# DEC8i-buscon.net
KiCad netlist of a schematic drawn in EAGLE
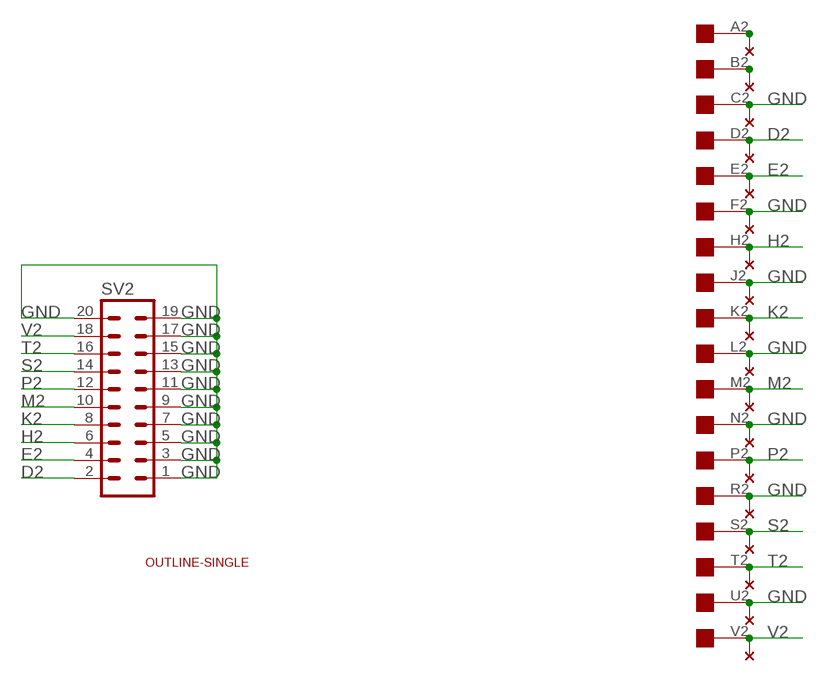
[diagram p0: schematic, sheet 1]

(export (version "E")
  (design (tool "Eeschema 10.0.6"))
  (components
    (comp (ref "SV2")
      (value "MA10-2")
      (footprint "eagle-import:MA10-2")
      (libsource (lib "eagle-import") (part "MA10-2"))
    )
    (comp (ref "U$4")
      (value "EDGE-1")
      (footprint "eagle-import:EDGE-CON1")
      (libsource (lib "eagle-import") (part "EDGE-1"))
    )
    (comp (ref "U$5")
      (value "THRU-HOLE1")
      (footprint "eagle-import:THRU-HOLE1")
      (libsource (lib "eagle-import") (part "THRU-HOLE1"))
    )
    (comp (ref "U$6")
      (value "OUTLINE-SINGLE")
      (footprint "eagle-import:SINGLE")
      (libsource (lib "eagle-import") (part "OUTLINE-SINGLE"))
    )
  )
  (nets
    (net (code "1") (name "/D2") (class "Default")
      (node (ref "SV2") (pin "2") (pinfunction "2_2") (pintype "passive"))
      (node (ref "U$4") (pin "D2") (pinfunction "1_D2") (pintype "bidirectional"))
      (node (ref "U$5") (pin "D2") (pinfunction "P$1_D2") (pintype "passive"))
    )
    (net (code "2") (name "/E2") (class "Default")
      (node (ref "SV2") (pin "4") (pinfunction "4_4") (pintype "passive"))
      (node (ref "U$4") (pin "E2") (pinfunction "1_E2") (pintype "bidirectional"))
      (node (ref "U$5") (pin "E2") (pinfunction "P$1_E2") (pintype "passive"))
    )
    (net (code "3") (name "/GND") (class "Default")
      (node (ref "SV2") (pin "1") (pinfunction "1_1") (pintype "passive"))
      (node (ref "SV2") (pin "11") (pinfunction "11_11") (pintype "passive"))
      (node (ref "SV2") (pin "13") (pinfunction "13_13") (pintype "passive"))
      (node (ref "SV2") (pin "15") (pinfunction "15_15") (pintype "passive"))
      (node (ref "SV2") (pin "17") (pinfunction "17_17") (pintype "passive"))
      (node (ref "SV2") (pin "19") (pinfunction "19_19") (pintype "passive"))
      (node (ref "SV2") (pin "20") (pinfunction "20_20") (pintype "passive"))
      (node (ref "SV2") (pin "3") (pinfunction "3_3") (pintype "passive"))
      (node (ref "SV2") (pin "5") (pinfunction "5_5") (pintype "passive"))
      (node (ref "SV2") (pin "7") (pinfunction "7_7") (pintype "passive"))
      (node (ref "SV2") (pin "9") (pinfunction "9_9") (pintype "passive"))
      (node (ref "U$4") (pin "C2") (pinfunction "1_C2") (pintype "bidirectional"))
      (node (ref "U$4") (pin "F2") (pinfunction "1_F2") (pintype "bidirectional"))
      (node (ref "U$4") (pin "J2") (pinfunction "1_J2") (pintype "bidirectional"))
      (node (ref "U$4") (pin "L2") (pinfunction "1_L2") (pintype "bidirectional"))
      (node (ref "U$4") (pin "N2") (pinfunction "1_N2") (pintype "bidirectional"))
      (node (ref "U$4") (pin "R2") (pinfunction "1_R2") (pintype "bidirectional"))
      (node (ref "U$4") (pin "U2") (pinfunction "1_U2") (pintype "bidirectional"))
      (node (ref "U$5") (pin "C2") (pinfunction "P$1_C2") (pintype "passive"))
      (node (ref "U$5") (pin "F2") (pinfunction "P$1_F2") (pintype "passive"))
      (node (ref "U$5") (pin "J2") (pinfunction "P$1_J2") (pintype "passive"))
      (node (ref "U$5") (pin "L2") (pinfunction "P$1_L2") (pintype "passive"))
      (node (ref "U$5") (pin "N2") (pinfunction "P$1_N2") (pintype "passive"))
      (node (ref "U$5") (pin "R2") (pinfunction "P$1_R2") (pintype "passive"))
      (node (ref "U$5") (pin "U2") (pinfunction "P$1_U2") (pintype "passive"))
    )
    (net (code "4") (name "/H2") (class "Default")
      (node (ref "SV2") (pin "6") (pinfunction "6_6") (pintype "passive"))
      (node (ref "U$4") (pin "H2") (pinfunction "1_H2") (pintype "bidirectional"))
      (node (ref "U$5") (pin "H2") (pinfunction "P$1_H2") (pintype "passive"))
    )
    (net (code "5") (name "/K2") (class "Default")
      (node (ref "SV2") (pin "8") (pinfunction "8_8") (pintype "passive"))
      (node (ref "U$4") (pin "K2") (pinfunction "1_K2") (pintype "bidirectional"))
      (node (ref "U$5") (pin "K2") (pinfunction "P$1_K2") (pintype "passive"))
    )
    (net (code "6") (name "/M2") (class "Default")
      (node (ref "SV2") (pin "10") (pinfunction "10_10") (pintype "passive"))
      (node (ref "U$4") (pin "M2") (pinfunction "1_M2") (pintype "bidirectional"))
      (node (ref "U$5") (pin "M2") (pinfunction "P$1_M2") (pintype "passive"))
    )
    (net (code "7") (name "/P2") (class "Default")
      (node (ref "SV2") (pin "12") (pinfunction "12_12") (pintype "passive"))
      (node (ref "U$4") (pin "P2") (pinfunction "1_P2") (pintype "bidirectional"))
      (node (ref "U$5") (pin "P2") (pinfunction "P$1_P2") (pintype "passive"))
    )
    (net (code "8") (name "/S2") (class "Default")
      (node (ref "SV2") (pin "14") (pinfunction "14_14") (pintype "passive"))
      (node (ref "U$4") (pin "S2") (pinfunction "1_S2") (pintype "bidirectional"))
      (node (ref "U$5") (pin "S2") (pinfunction "P$1_S2") (pintype "passive"))
    )
    (net (code "9") (name "/T2") (class "Default")
      (node (ref "SV2") (pin "16") (pinfunction "16_16") (pintype "passive"))
      (node (ref "U$4") (pin "T2") (pinfunction "1_T2") (pintype "bidirectional"))
      (node (ref "U$5") (pin "T2") (pinfunction "P$1_T2") (pintype "passive"))
    )
    (net (code "10") (name "/V2") (class "Default")
      (node (ref "SV2") (pin "18") (pinfunction "18_18") (pintype "passive"))
      (node (ref "U$4") (pin "V2") (pinfunction "1_V2") (pintype "bidirectional"))
      (node (ref "U$5") (pin "V2") (pinfunction "P$1_V2") (pintype "passive"))
    )
    (net (code "11") (name "Net-(U$4A-1)") (class "Default")
      (node (ref "U$4") (pin "A2") (pinfunction "1_A2") (pintype "bidirectional"))
      (node (ref "U$5") (pin "A2") (pinfunction "P$1_A2") (pintype "passive"))
    )
    (net (code "12") (name "Net-(U$4B-1)") (class "Default")
      (node (ref "U$4") (pin "B2") (pinfunction "1_B2") (pintype "bidirectional"))
      (node (ref "U$5") (pin "B2") (pinfunction "P$1_B2") (pintype "passive"))
    )
  )
)
